# BartendingRobotPCB.net
KiCad netlist of a schematic drawn in EAGLE
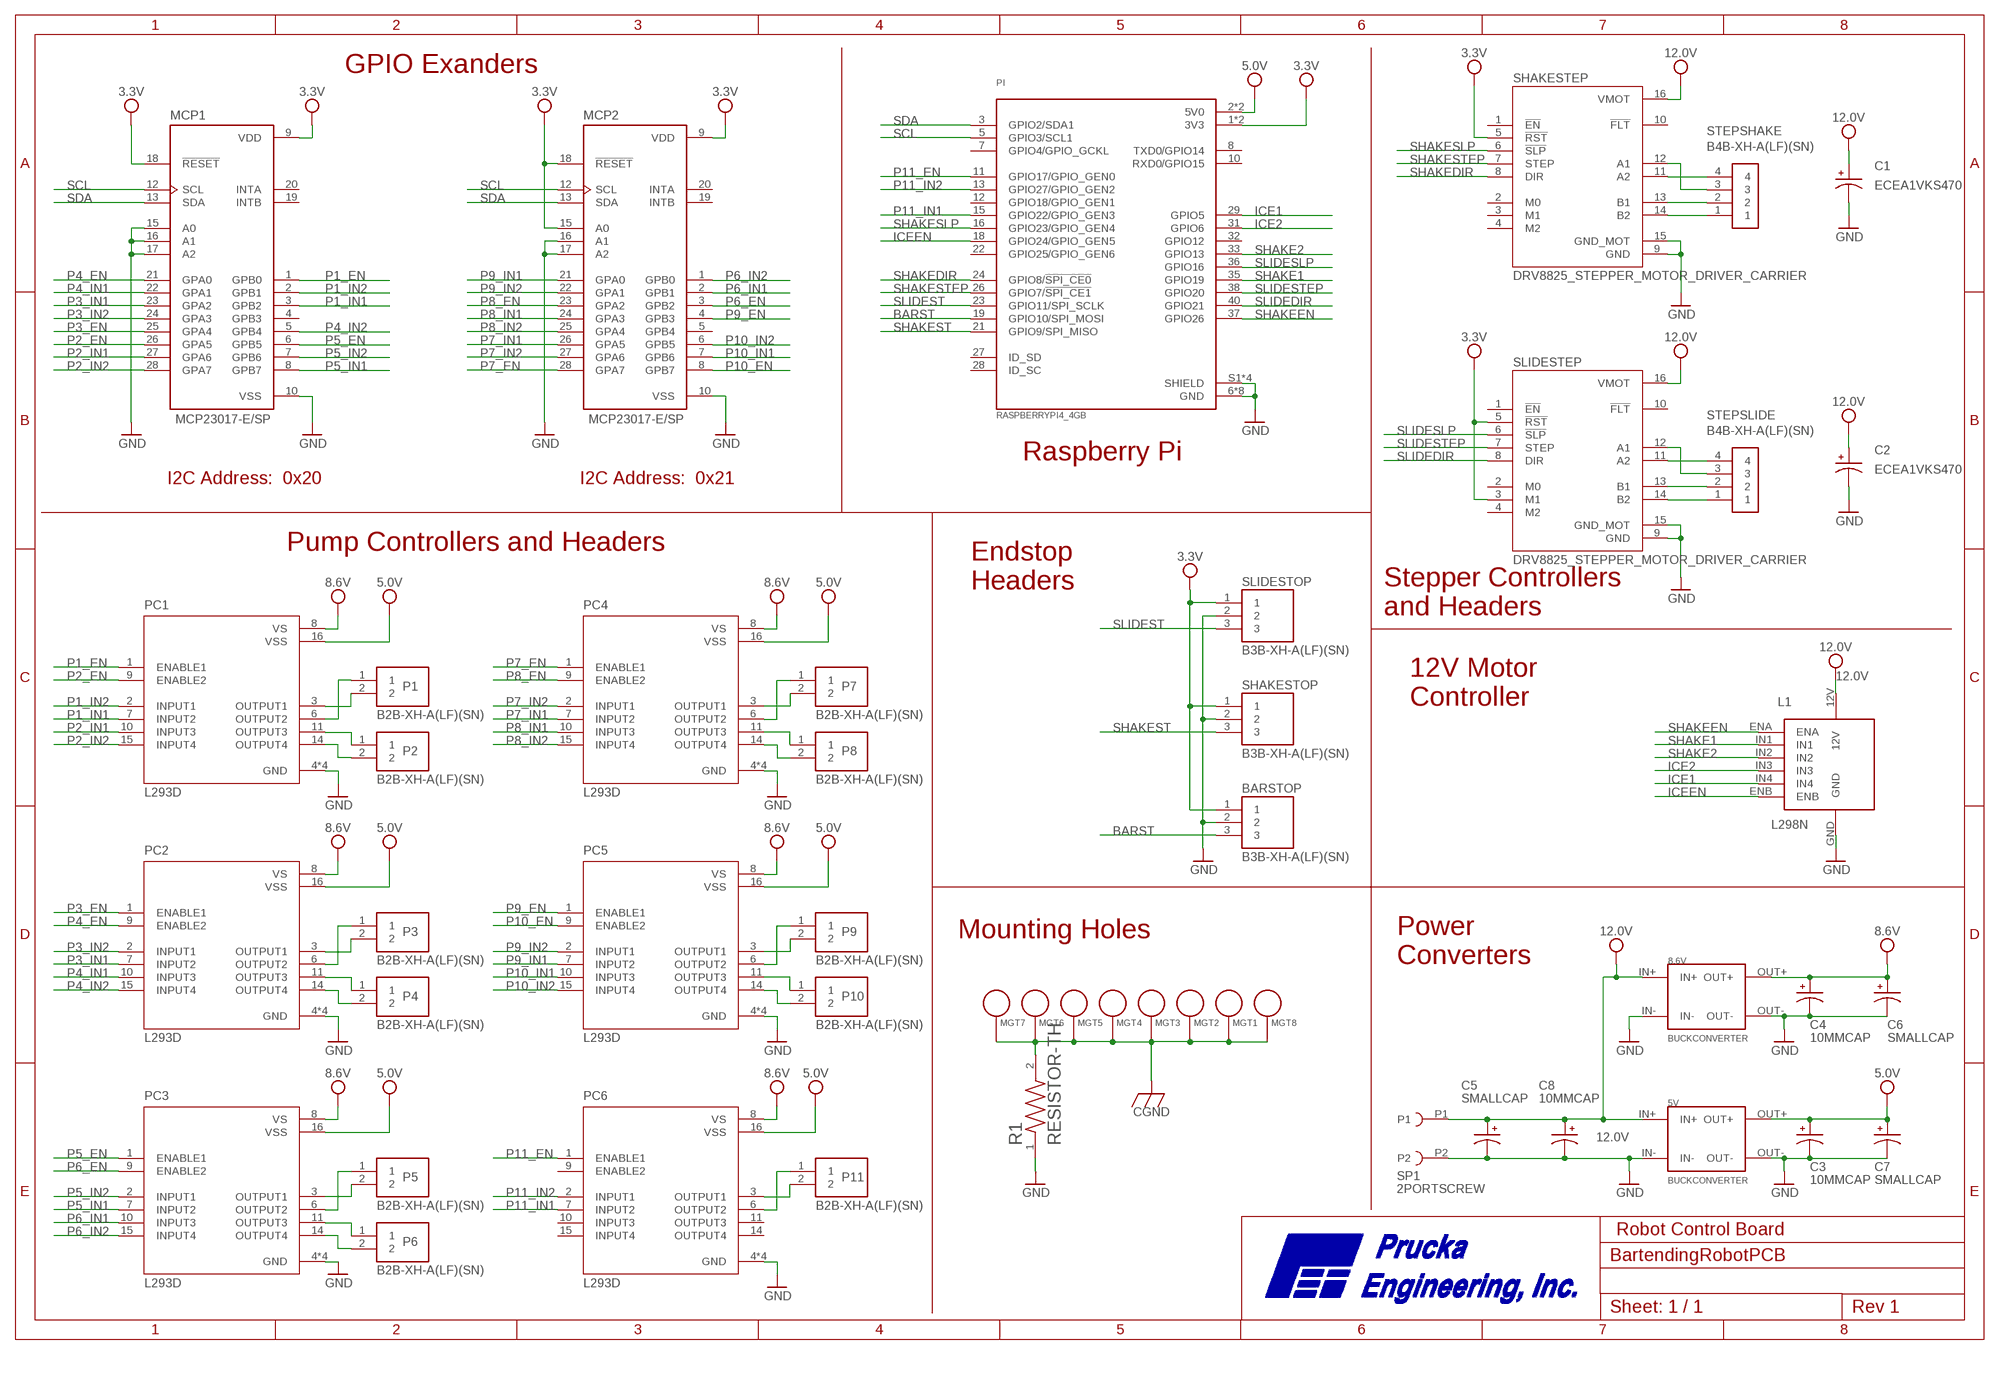
[diagram p0: schematic, sheet 1]

(export (version "E")
  (design (tool "Eeschema 10.0.6"))
  (components
    (comp (ref "5V")
      (value "BUCKCONVERTER")
      (footprint "eagle-import:BUCKCONVERTER")
      (libsource (lib "eagle-import") (part "BUCKCONVERTER"))
    )
    (comp (ref "8.6V")
      (value "BUCKCONVERTER")
      (footprint "eagle-import:BUCKCONVERTER")
      (libsource (lib "eagle-import") (part "BUCKCONVERTER"))
    )
    (comp (ref "BARSTOP")
      (value "B3B-XH-A(LF)(SN)")
      (footprint "eagle-import:JST_B3B-XH-A(LF)(SN)")
      (fields (field (name "MF") "JST Sales"))
      (libsource (lib "eagle-import") (part "B3B-XH-A(LF)(SN)"))
    )
    (comp (ref "C1")
      (value "ECEA1VKS470")
      (footprint "eagle-import:CAPPRD250W45D800H500")
      (fields (field (name "MF") "PANASONIC"))
      (libsource (lib "eagle-import") (part "ECEA1VKS470"))
    )
    (comp (ref "C2")
      (value "ECEA1VKS470")
      (footprint "eagle-import:CAPPRD250W45D800H500")
      (fields (field (name "MF") "PANASONIC"))
      (libsource (lib "eagle-import") (part "ECEA1VKS470"))
    )
    (comp (ref "C3")
      (value "10MMCAP")
      (footprint "eagle-import:10MMCAP")
      (libsource (lib "eagle-import") (part "10MMCAP"))
    )
    (comp (ref "C4")
      (value "10MMCAP")
      (footprint "eagle-import:10MMCAP")
      (libsource (lib "eagle-import") (part "10MMCAP"))
    )
    (comp (ref "C5")
      (value "SMALLCAP")
      (footprint "eagle-import:SMALLCAP")
      (libsource (lib "eagle-import") (part "SMALLCAP"))
    )
    (comp (ref "C6")
      (value "SMALLCAP")
      (footprint "eagle-import:SMALLCAP")
      (libsource (lib "eagle-import") (part "SMALLCAP"))
    )
    (comp (ref "C7")
      (value "SMALLCAP")
      (footprint "eagle-import:SMALLCAP")
      (libsource (lib "eagle-import") (part "SMALLCAP"))
    )
    (comp (ref "C8")
      (value "10MMCAP")
      (footprint "eagle-import:10MMCAP")
      (libsource (lib "eagle-import") (part "10MMCAP"))
    )
    (comp (ref "L1")
      (value "L298N")
      (footprint "eagle-import:L298N")
      (libsource (lib "eagle-import") (part "L298N"))
    )
    (comp (ref "MCP1")
      (value "MCP23017-E/SP")
      (footprint "eagle-import:DIP787W45P254L3556H508Q28")
      (fields (field (name "MF") "Microchip"))
      (libsource (lib "eagle-import") (part "MCP23017-E/SP"))
    )
    (comp (ref "MCP2")
      (value "MCP23017-E/SP")
      (footprint "eagle-import:DIP787W45P254L3556H508Q28")
      (fields (field (name "MF") "Microchip"))
      (libsource (lib "eagle-import") (part "MCP23017-E/SP"))
    )
    (comp (ref "MGT1")
      (value "MOUNTING_HOLE")
      (footprint "eagle-import:MOUNTING_HOLE")
      (libsource (lib "eagle-import") (part "MOUNTING_HOLE"))
    )
    (comp (ref "MGT2")
      (value "MOUNTING_HOLE")
      (footprint "eagle-import:MOUNTING_HOLE")
      (libsource (lib "eagle-import") (part "MOUNTING_HOLE"))
    )
    (comp (ref "MGT3")
      (value "MOUNTING_HOLE")
      (footprint "eagle-import:MOUNTING_HOLE")
      (libsource (lib "eagle-import") (part "MOUNTING_HOLE"))
    )
    (comp (ref "MGT4")
      (value "MOUNTING_HOLE")
      (footprint "eagle-import:MOUNTING_HOLE")
      (libsource (lib "eagle-import") (part "MOUNTING_HOLE"))
    )
    (comp (ref "MGT5")
      (value "MOUNTING_HOLE")
      (footprint "eagle-import:MOUNTING_HOLE")
      (libsource (lib "eagle-import") (part "MOUNTING_HOLE"))
    )
    (comp (ref "MGT6")
      (value "MOUNTING_HOLE")
      (footprint "eagle-import:MOUNTING_HOLE")
      (libsource (lib "eagle-import") (part "MOUNTING_HOLE"))
    )
    (comp (ref "MGT7")
      (value "MOUNTING_HOLE")
      (footprint "eagle-import:MOUNTING_HOLE")
      (libsource (lib "eagle-import") (part "MOUNTING_HOLE"))
    )
    (comp (ref "MGT8")
      (value "MOUNTING_HOLE")
      (footprint "eagle-import:MOUNTING_HOLE")
      (libsource (lib "eagle-import") (part "MOUNTING_HOLE"))
    )
    (comp (ref "P1")
      (value "B2B-XH-A(LF)(SN)")
      (footprint "eagle-import:JST_B2B-XH-A(LF)(SN)")
      (fields (field (name "MF") "JST Sales"))
      (libsource (lib "eagle-import") (part "B2B-XH-A(LF)(SN)"))
    )
    (comp (ref "P2")
      (value "B2B-XH-A(LF)(SN)")
      (footprint "eagle-import:JST_B2B-XH-A(LF)(SN)")
      (fields (field (name "MF") "JST Sales"))
      (libsource (lib "eagle-import") (part "B2B-XH-A(LF)(SN)"))
    )
    (comp (ref "P3")
      (value "B2B-XH-A(LF)(SN)")
      (footprint "eagle-import:JST_B2B-XH-A(LF)(SN)")
      (fields (field (name "MF") "JST Sales"))
      (libsource (lib "eagle-import") (part "B2B-XH-A(LF)(SN)"))
    )
    (comp (ref "P4")
      (value "B2B-XH-A(LF)(SN)")
      (footprint "eagle-import:JST_B2B-XH-A(LF)(SN)")
      (fields (field (name "MF") "JST Sales"))
      (libsource (lib "eagle-import") (part "B2B-XH-A(LF)(SN)"))
    )
    (comp (ref "P5")
      (value "B2B-XH-A(LF)(SN)")
      (footprint "eagle-import:JST_B2B-XH-A(LF)(SN)")
      (fields (field (name "MF") "JST Sales"))
      (libsource (lib "eagle-import") (part "B2B-XH-A(LF)(SN)"))
    )
    (comp (ref "P6")
      (value "B2B-XH-A(LF)(SN)")
      (footprint "eagle-import:JST_B2B-XH-A(LF)(SN)")
      (fields (field (name "MF") "JST Sales"))
      (libsource (lib "eagle-import") (part "B2B-XH-A(LF)(SN)"))
    )
    (comp (ref "P7")
      (value "B2B-XH-A(LF)(SN)")
      (footprint "eagle-import:JST_B2B-XH-A(LF)(SN)")
      (fields (field (name "MF") "JST Sales"))
      (libsource (lib "eagle-import") (part "B2B-XH-A(LF)(SN)"))
    )
    (comp (ref "P8")
      (value "B2B-XH-A(LF)(SN)")
      (footprint "eagle-import:JST_B2B-XH-A(LF)(SN)")
      (fields (field (name "MF") "JST Sales"))
      (libsource (lib "eagle-import") (part "B2B-XH-A(LF)(SN)"))
    )
    (comp (ref "P9")
      (value "B2B-XH-A(LF)(SN)")
      (footprint "eagle-import:JST_B2B-XH-A(LF)(SN)")
      (fields (field (name "MF") "JST Sales"))
      (libsource (lib "eagle-import") (part "B2B-XH-A(LF)(SN)"))
    )
    (comp (ref "P10")
      (value "B2B-XH-A(LF)(SN)")
      (footprint "eagle-import:JST_B2B-XH-A(LF)(SN)")
      (fields (field (name "MF") "JST Sales"))
      (libsource (lib "eagle-import") (part "B2B-XH-A(LF)(SN)"))
    )
    (comp (ref "P11")
      (value "B2B-XH-A(LF)(SN)")
      (footprint "eagle-import:JST_B2B-XH-A(LF)(SN)")
      (fields (field (name "MF") "JST Sales"))
      (libsource (lib "eagle-import") (part "B2B-XH-A(LF)(SN)"))
    )
    (comp (ref "PC1")
      (value "L293D")
      (footprint "eagle-import:DIP880W50P254L2000H510Q16")
      (fields (field (name "MANUFACTURER") "ST Microelectronics"))
      (libsource (lib "eagle-import") (part "L293D"))
    )
    (comp (ref "PC2")
      (value "L293D")
      (footprint "eagle-import:DIP880W50P254L2000H510Q16")
      (fields (field (name "MANUFACTURER") "ST Microelectronics"))
      (libsource (lib "eagle-import") (part "L293D"))
    )
    (comp (ref "PC3")
      (value "L293D")
      (footprint "eagle-import:DIP880W50P254L2000H510Q16")
      (fields (field (name "MANUFACTURER") "ST Microelectronics"))
      (libsource (lib "eagle-import") (part "L293D"))
    )
    (comp (ref "PC4")
      (value "L293D")
      (footprint "eagle-import:DIP880W50P254L2000H510Q16")
      (fields (field (name "MANUFACTURER") "ST Microelectronics"))
      (libsource (lib "eagle-import") (part "L293D"))
    )
    (comp (ref "PC5")
      (value "L293D")
      (footprint "eagle-import:DIP880W50P254L2000H510Q16")
      (fields (field (name "MANUFACTURER") "ST Microelectronics"))
      (libsource (lib "eagle-import") (part "L293D"))
    )
    (comp (ref "PC6")
      (value "L293D")
      (footprint "eagle-import:DIP880W50P254L2000H510Q16")
      (fields (field (name "MANUFACTURER") "ST Microelectronics"))
      (libsource (lib "eagle-import") (part "L293D"))
    )
    (comp (ref "PI")
      (value "RASPBERRYPI4_4GB")
      (footprint "eagle-import:MODULE_RASPBERRYPI4_4GB")
      (fields (field (name "MANUFACTURER") "Raspberry Pi"))
      (libsource (lib "eagle-import") (part "RASPBERRYPI4_4GB"))
    )
    (comp (ref "R1")
      (value "RESISTOR-TH")
      (footprint "eagle-import:RESAD700W45L350D185")
      (fields (field (name "MANUFACTURER") "TE Connectivity"))
      (libsource (lib "eagle-import") (part "RESISTOR-TH"))
    )
    (comp (ref "SHAKESTEP")
      (value "DRV8825_STEPPER_MOTOR_DRIVER_CARRIER")
      (footprint "eagle-import:IC_DRV8825_STEPPER_MOTOR_DRIVER_CARRIER")
      (fields (field (name "MF") "Pololu") (field (name "MP") "DRV8825 STEPPER MOTOR DRIVER CARRIER"))
      (libsource (lib "eagle-import") (part "DRV8825_STEPPER_MOTOR_DRIVER_CARRIER"))
    )
    (comp (ref "SHAKESTOP")
      (value "B3B-XH-A(LF)(SN)")
      (footprint "eagle-import:JST_B3B-XH-A(LF)(SN)")
      (fields (field (name "MF") "JST Sales"))
      (libsource (lib "eagle-import") (part "B3B-XH-A(LF)(SN)"))
    )
    (comp (ref "SLIDESTEP")
      (value "DRV8825_STEPPER_MOTOR_DRIVER_CARRIER")
      (footprint "eagle-import:IC_DRV8825_STEPPER_MOTOR_DRIVER_CARRIER")
      (fields (field (name "MF") "Pololu") (field (name "MP") "DRV8825 STEPPER MOTOR DRIVER CARRIER"))
      (libsource (lib "eagle-import") (part "DRV8825_STEPPER_MOTOR_DRIVER_CARRIER"))
    )
    (comp (ref "SLIDESTOP")
      (value "B3B-XH-A(LF)(SN)")
      (footprint "eagle-import:JST_B3B-XH-A(LF)(SN)")
      (fields (field (name "MF") "JST Sales"))
      (libsource (lib "eagle-import") (part "B3B-XH-A(LF)(SN)"))
    )
    (comp (ref "SP1")
      (value "2PORTSCREW")
      (footprint "eagle-import:2PORTSCREW")
      (libsource (lib "eagle-import") (part "2PORTSCREW"))
    )
    (comp (ref "STEPSHAKE")
      (value "B4B-XH-A(LF)(SN)")
      (footprint "eagle-import:JST_B4B-XH-A(LF)(SN)")
      (fields (field (name "MANUFACTURER") " JST Sales America Inc"))
      (libsource (lib "eagle-import") (part "B4B-XH-A(LF)(SN)"))
    )
    (comp (ref "STEPSLIDE")
      (value "B4B-XH-A(LF)(SN)")
      (footprint "eagle-import:JST_B4B-XH-A(LF)(SN)")
      (fields (field (name "MANUFACTURER") " JST Sales America Inc"))
      (libsource (lib "eagle-import") (part "B4B-XH-A(LF)(SN)"))
    )
  )
  (nets
    (net (code "1") (name "/BARST") (class "Default")
      (node (ref "BARSTOP") (pin "3") (pinfunction "3_3") (pintype "passive"))
      (node (ref "PI") (pin "19") (pinfunction "GPIO10/SPI_MOSI_19") (pintype "bidirectional"))
    )
    (net (code "2") (name "/ICE1") (class "Default")
      (node (ref "L1") (pin "IN4") (pinfunction "IN4_IN4") (pintype "bidirectional"))
      (node (ref "PI") (pin "29") (pinfunction "GPIO5_29") (pintype "bidirectional"))
    )
    (net (code "3") (name "/ICE2") (class "Default")
      (node (ref "L1") (pin "IN3") (pinfunction "IN3_IN3") (pintype "bidirectional"))
      (node (ref "PI") (pin "31") (pinfunction "GPIO6_31") (pintype "bidirectional"))
    )
    (net (code "4") (name "/ICEEN") (class "Default")
      (node (ref "L1") (pin "ENB") (pinfunction "ENB_ENB") (pintype "bidirectional"))
      (node (ref "PI") (pin "18") (pinfunction "GPIO24/GPIO_GEN5_18") (pintype "bidirectional"))
    )
    (net (code "5") (name "/P1_EN") (class "Default")
      (node (ref "MCP1") (pin "1") (pinfunction "GPB0_1") (pintype "bidirectional"))
      (node (ref "PC1") (pin "1") (pinfunction "ENABLE1_1") (pintype "input"))
    )
    (net (code "6") (name "/P1_IN1") (class "Default")
      (node (ref "MCP1") (pin "3") (pinfunction "GPB2_3") (pintype "bidirectional"))
      (node (ref "PC1") (pin "7") (pinfunction "INPUT2_7") (pintype "input"))
    )
    (net (code "7") (name "/P1_IN2") (class "Default")
      (node (ref "MCP1") (pin "2") (pinfunction "GPB1_2") (pintype "bidirectional"))
      (node (ref "PC1") (pin "2") (pinfunction "INPUT1_2") (pintype "input"))
    )
    (net (code "8") (name "/P2_EN") (class "Default")
      (node (ref "MCP1") (pin "26") (pinfunction "GPA5_26") (pintype "bidirectional"))
      (node (ref "PC1") (pin "9") (pinfunction "ENABLE2_9") (pintype "input"))
    )
    (net (code "9") (name "/P2_IN1") (class "Default")
      (node (ref "MCP1") (pin "27") (pinfunction "GPA6_27") (pintype "bidirectional"))
      (node (ref "PC1") (pin "10") (pinfunction "INPUT3_10") (pintype "input"))
    )
    (net (code "10") (name "/P2_IN2") (class "Default")
      (node (ref "MCP1") (pin "28") (pinfunction "GPA7_28") (pintype "bidirectional"))
      (node (ref "PC1") (pin "15") (pinfunction "INPUT4_15") (pintype "input"))
    )
    (net (code "11") (name "/P3_EN") (class "Default")
      (node (ref "MCP1") (pin "25") (pinfunction "GPA4_25") (pintype "bidirectional"))
      (node (ref "PC2") (pin "1") (pinfunction "ENABLE1_1") (pintype "input"))
    )
    (net (code "12") (name "/P3_IN1") (class "Default")
      (node (ref "MCP1") (pin "23") (pinfunction "GPA2_23") (pintype "bidirectional"))
      (node (ref "PC2") (pin "7") (pinfunction "INPUT2_7") (pintype "input"))
    )
    (net (code "13") (name "/P3_IN2") (class "Default")
      (node (ref "MCP1") (pin "24") (pinfunction "GPA3_24") (pintype "bidirectional"))
      (node (ref "PC2") (pin "2") (pinfunction "INPUT1_2") (pintype "input"))
    )
    (net (code "14") (name "/P4_EN") (class "Default")
      (node (ref "MCP1") (pin "21") (pinfunction "GPA0_21") (pintype "bidirectional"))
      (node (ref "PC2") (pin "9") (pinfunction "ENABLE2_9") (pintype "input"))
    )
    (net (code "15") (name "/P4_IN1") (class "Default")
      (node (ref "MCP1") (pin "22") (pinfunction "GPA1_22") (pintype "bidirectional"))
      (node (ref "PC2") (pin "10") (pinfunction "INPUT3_10") (pintype "input"))
    )
    (net (code "16") (name "/P4_IN2") (class "Default")
      (node (ref "MCP1") (pin "5") (pinfunction "GPB4_5") (pintype "bidirectional"))
      (node (ref "PC2") (pin "15") (pinfunction "INPUT4_15") (pintype "input"))
    )
    (net (code "17") (name "/P5_EN") (class "Default")
      (node (ref "MCP1") (pin "6") (pinfunction "GPB5_6") (pintype "bidirectional"))
      (node (ref "PC3") (pin "1") (pinfunction "ENABLE1_1") (pintype "input"))
    )
    (net (code "18") (name "/P5_IN1") (class "Default")
      (node (ref "MCP1") (pin "8") (pinfunction "GPB7_8") (pintype "bidirectional"))
      (node (ref "PC3") (pin "7") (pinfunction "INPUT2_7") (pintype "input"))
    )
    (net (code "19") (name "/P5_IN2") (class "Default")
      (node (ref "MCP1") (pin "7") (pinfunction "GPB6_7") (pintype "bidirectional"))
      (node (ref "PC3") (pin "2") (pinfunction "INPUT1_2") (pintype "input"))
    )
    (net (code "20") (name "/P6_EN") (class "Default")
      (node (ref "MCP2") (pin "3") (pinfunction "GPB2_3") (pintype "bidirectional"))
      (node (ref "PC3") (pin "9") (pinfunction "ENABLE2_9") (pintype "input"))
    )
    (net (code "21") (name "/P6_IN1") (class "Default")
      (node (ref "MCP2") (pin "2") (pinfunction "GPB1_2") (pintype "bidirectional"))
      (node (ref "PC3") (pin "10") (pinfunction "INPUT3_10") (pintype "input"))
    )
    (net (code "22") (name "/P6_IN2") (class "Default")
      (node (ref "MCP2") (pin "1") (pinfunction "GPB0_1") (pintype "bidirectional"))
      (node (ref "PC3") (pin "15") (pinfunction "INPUT4_15") (pintype "input"))
    )
    (net (code "23") (name "/P7_EN") (class "Default")
      (node (ref "MCP2") (pin "28") (pinfunction "GPA7_28") (pintype "bidirectional"))
      (node (ref "PC4") (pin "1") (pinfunction "ENABLE1_1") (pintype "input"))
    )
    (net (code "24") (name "/P7_IN1") (class "Default")
      (node (ref "MCP2") (pin "26") (pinfunction "GPA5_26") (pintype "bidirectional"))
      (node (ref "PC4") (pin "7") (pinfunction "INPUT2_7") (pintype "input"))
    )
    (net (code "25") (name "/P7_IN2") (class "Default")
      (node (ref "MCP2") (pin "27") (pinfunction "GPA6_27") (pintype "bidirectional"))
      (node (ref "PC4") (pin "2") (pinfunction "INPUT1_2") (pintype "input"))
    )
    (net (code "26") (name "/P8_EN") (class "Default")
      (node (ref "MCP2") (pin "23") (pinfunction "GPA2_23") (pintype "bidirectional"))
      (node (ref "PC4") (pin "9") (pinfunction "ENABLE2_9") (pintype "input"))
    )
    (net (code "27") (name "/P8_IN1") (class "Default")
      (node (ref "MCP2") (pin "24") (pinfunction "GPA3_24") (pintype "bidirectional"))
      (node (ref "PC4") (pin "10") (pinfunction "INPUT3_10") (pintype "input"))
    )
    (net (code "28") (name "/P8_IN2") (class "Default")
      (node (ref "MCP2") (pin "25") (pinfunction "GPA4_25") (pintype "bidirectional"))
      (node (ref "PC4") (pin "15") (pinfunction "INPUT4_15") (pintype "input"))
    )
    (net (code "29") (name "/P9_EN") (class "Default")
      (node (ref "MCP2") (pin "4") (pinfunction "GPB3_4") (pintype "bidirectional"))
      (node (ref "PC5") (pin "1") (pinfunction "ENABLE1_1") (pintype "input"))
    )
    (net (code "30") (name "/P9_IN1") (class "Default")
      (node (ref "MCP2") (pin "21") (pinfunction "GPA0_21") (pintype "bidirectional"))
      (node (ref "PC5") (pin "7") (pinfunction "INPUT2_7") (pintype "input"))
    )
    (net (code "31") (name "/P9_IN2") (class "Default")
      (node (ref "MCP2") (pin "22") (pinfunction "GPA1_22") (pintype "bidirectional"))
      (node (ref "PC5") (pin "2") (pinfunction "INPUT1_2") (pintype "input"))
    )
    (net (code "32") (name "/P10_EN") (class "Default")
      (node (ref "MCP2") (pin "8") (pinfunction "GPB7_8") (pintype "bidirectional"))
      (node (ref "PC5") (pin "9") (pinfunction "ENABLE2_9") (pintype "input"))
    )
    (net (code "33") (name "/P10_IN1") (class "Default")
      (node (ref "MCP2") (pin "7") (pinfunction "GPB6_7") (pintype "bidirectional"))
      (node (ref "PC5") (pin "10") (pinfunction "INPUT3_10") (pintype "input"))
    )
    (net (code "34") (name "/P10_IN2") (class "Default")
      (node (ref "MCP2") (pin "6") (pinfunction "GPB5_6") (pintype "bidirectional"))
      (node (ref "PC5") (pin "15") (pinfunction "INPUT4_15") (pintype "input"))
    )
    (net (code "35") (name "/P11_EN") (class "Default")
      (node (ref "PC6") (pin "1") (pinfunction "ENABLE1_1") (pintype "input"))
      (node (ref "PI") (pin "11") (pinfunction "GPIO17/GPIO_GEN0_11") (pintype "bidirectional"))
    )
    (net (code "36") (name "/P11_IN1") (class "Default")
      (node (ref "PC6") (pin "7") (pinfunction "INPUT2_7") (pintype "input"))
      (node (ref "PI") (pin "15") (pinfunction "GPIO22/GPIO_GEN3_15") (pintype "bidirectional"))
    )
    (net (code "37") (name "/P11_IN2") (class "Default")
      (node (ref "PC6") (pin "2") (pinfunction "INPUT1_2") (pintype "input"))
      (node (ref "PI") (pin "13") (pinfunction "GPIO27/GPIO_GEN2_13") (pintype "bidirectional"))
    )
    (net (code "38") (name "/SCL") (class "Default")
      (node (ref "MCP1") (pin "12") (pinfunction "SCL_12") (pintype "input"))
      (node (ref "MCP2") (pin "12") (pinfunction "SCL_12") (pintype "input"))
      (node (ref "PI") (pin "5") (pinfunction "GPIO3/SCL1_5") (pintype "bidirectional"))
    )
    (net (code "39") (name "/SDA") (class "Default")
      (node (ref "MCP1") (pin "13") (pinfunction "SDA_13") (pintype "bidirectional"))
      (node (ref "MCP2") (pin "13") (pinfunction "SDA_13") (pintype "bidirectional"))
      (node (ref "PI") (pin "3") (pinfunction "GPIO2/SDA1_3") (pintype "bidirectional"))
    )
    (net (code "40") (name "/SHAKE1") (class "Default")
      (node (ref "L1") (pin "IN1") (pinfunction "IN1_IN1") (pintype "bidirectional"))
      (node (ref "PI") (pin "35") (pinfunction "GPIO19_35") (pintype "bidirectional"))
    )
    (net (code "41") (name "/SHAKE2") (class "Default")
      (node (ref "L1") (pin "IN2") (pinfunction "IN2_IN2") (pintype "bidirectional"))
      (node (ref "PI") (pin "33") (pinfunction "GPIO13_33") (pintype "bidirectional"))
    )
    (net (code "42") (name "/SHAKEDIR") (class "Default")
      (node (ref "PI") (pin "24") (pinfunction "GPIO8/~{SPI_CE0}_24") (pintype "bidirectional"))
      (node (ref "SHAKESTEP") (pin "8") (pinfunction "DIR_8") (pintype "input"))
    )
    (net (code "43") (name "/SHAKEEN") (class "Default")
      (node (ref "L1") (pin "ENA") (pinfunction "ENA_ENA") (pintype "bidirectional"))
      (node (ref "PI") (pin "37") (pinfunction "GPIO26_37") (pintype "bidirectional"))
    )
    (net (code "44") (name "/SHAKESLP") (class "Default")
      (node (ref "PI") (pin "16") (pinfunction "GPIO23/GPIO_GEN4_16") (pintype "bidirectional"))
      (node (ref "SHAKESTEP") (pin "6") (pinfunction "~{SLP}_6") (pintype "input"))
    )
    (net (code "45") (name "/SHAKEST") (class "Default")
      (node (ref "PI") (pin "21") (pinfunction "GPIO9/SPI_MISO_21") (pintype "bidirectional"))
      (node (ref "SHAKESTOP") (pin "3") (pinfunction "3_3") (pintype "passive"))
    )
    (net (code "46") (name "/SHAKESTEP") (class "Default")
      (node (ref "PI") (pin "26") (pinfunction "GPIO7/~{SPI_CE1}_26") (pintype "bidirectional"))
      (node (ref "SHAKESTEP") (pin "7") (pinfunction "STEP_7") (pintype "input"))
    )
    (net (code "47") (name "/SLIDEDIR") (class "Default")
      (node (ref "PI") (pin "40") (pinfunction "GPIO21_40") (pintype "bidirectional"))
      (node (ref "SLIDESTEP") (pin "8") (pinfunction "DIR_8") (pintype "input"))
    )
    (net (code "48") (name "/SLIDESLP") (class "Default")
      (node (ref "PI") (pin "36") (pinfunction "GPIO16_36") (pintype "bidirectional"))
      (node (ref "SLIDESTEP") (pin "6") (pinfunction "~{SLP}_6") (pintype "input"))
    )
    (net (code "49") (name "/SLIDEST") (class "Default")
      (node (ref "PI") (pin "23") (pinfunction "GPIO11/SPI_SCLK_23") (pintype "bidirectional"))
      (node (ref "SLIDESTOP") (pin "3") (pinfunction "3_3") (pintype "passive"))
    )
    (net (code "50") (name "/SLIDESTEP") (class "Default")
      (node (ref "PI") (pin "38") (pinfunction "GPIO20_38") (pintype "bidirectional"))
      (node (ref "SLIDESTEP") (pin "7") (pinfunction "STEP_7") (pintype "input"))
    )
    (net (code "51") (name "3.3V") (class "Default")
      (node (ref "BARSTOP") (pin "1") (pinfunction "1_1") (pintype "passive"))
      (node (ref "MCP1") (pin "18") (pinfunction "~{RESET}_18") (pintype "input"))
      (node (ref "MCP1") (pin "9") (pinfunction "VDD_9") (pintype "power_in"))
      (node (ref "MCP2") (pin "15") (pinfunction "A0_15") (pintype "input"))
      (node (ref "MCP2") (pin "18") (pinfunction "~{RESET}_18") (pintype "input"))
      (node (ref "MCP2") (pin "9") (pinfunction "VDD_9") (pintype "power_in"))
      (node (ref "PI") (pin "1") (pinfunction "3V3_1") (pintype "power_in"))
      (node (ref "PI") (pin "17") (pinfunction "3V3_17") (pintype "power_in"))
      (node (ref "SHAKESTEP") (pin "5") (pinfunction "~{RST}_5") (pintype "input"))
      (node (ref "SHAKESTOP") (pin "1") (pinfunction "1_1") (pintype "passive"))
      (node (ref "SLIDESTEP") (pin "3") (pinfunction "M1_3") (pintype "input"))
      (node (ref "SLIDESTEP") (pin "5") (pinfunction "~{RST}_5") (pintype "input"))
      (node (ref "SLIDESTOP") (pin "1") (pinfunction "1_1") (pintype "passive"))
    )
    (net (code "52") (name "5.0V") (class "Default")
      (node (ref "5V") (pin "OUT+") (pinfunction "OUT+_OUT+") (pintype "bidirectional"))
      (node (ref "C3") (pin "+") (pinfunction "P_+") (pintype "passive"))
      (node (ref "C7") (pin "+") (pinfunction "P_+") (pintype "passive"))
      (node (ref "PC1") (pin "16") (pinfunction "VSS_16") (pintype "power_in"))
      (node (ref "PC2") (pin "16") (pinfunction "VSS_16") (pintype "power_in"))
      (node (ref "PC3") (pin "16") (pinfunction "VSS_16") (pintype "power_in"))
      (node (ref "PC4") (pin "16") (pinfunction "VSS_16") (pintype "power_in"))
      (node (ref "PC5") (pin "16") (pinfunction "VSS_16") (pintype "power_in"))
      (node (ref "PC6") (pin "16") (pinfunction "VSS_16") (pintype "power_in"))
      (node (ref "PI") (pin "2") (pinfunction "5V0_2") (pintype "power_in"))
      (node (ref "PI") (pin "4") (pinfunction "5V0_4") (pintype "power_in"))
    )
    (net (code "53") (name "8.6V") (class "Default")
      (node (ref "8.6V") (pin "OUT+") (pinfunction "OUT+_OUT+") (pintype "bidirectional"))
      (node (ref "C4") (pin "+") (pinfunction "P_+") (pintype "passive"))
      (node (ref "C6") (pin "+") (pinfunction "P_+") (pintype "passive"))
      (node (ref "PC1") (pin "8") (pinfunction "VS_8") (pintype "power_in"))
      (node (ref "PC2") (pin "8") (pinfunction "VS_8") (pintype "power_in"))
      (node (ref "PC3") (pin "8") (pinfunction "VS_8") (pintype "power_in"))
      (node (ref "PC4") (pin "8") (pinfunction "VS_8") (pintype "power_in"))
      (node (ref "PC5") (pin "8") (pinfunction "VS_8") (pintype "power_in"))
      (node (ref "PC6") (pin "8") (pinfunction "VS_8") (pintype "power_in"))
    )
    (net (code "54") (name "12.0V") (class "Default")
      (node (ref "5V") (pin "IN+") (pinfunction "IN+_IN+") (pintype "bidirectional"))
      (node (ref "8.6V") (pin "IN+") (pinfunction "IN+_IN+") (pintype "bidirectional"))
      (node (ref "C1") (pin "P") (pinfunction "P_P") (pintype "passive"))
      (node (ref "C2") (pin "P") (pinfunction "P_P") (pintype "passive"))
      (node (ref "C5") (pin "+") (pinfunction "P_+") (pintype "passive"))
      (node (ref "C8") (pin "+") (pinfunction "P_+") (pintype "passive"))
      (node (ref "L1") (pin "12V") (pinfunction "12V_12V") (pintype "bidirectional"))
      (node (ref "SHAKESTEP") (pin "16") (pinfunction "VMOT_16") (pintype "power_in"))
      (node (ref "SLIDESTEP") (pin "16") (pinfunction "VMOT_16") (pintype "power_in"))
      (node (ref "SP1") (pin "P1") (pinfunction "P1_P1") (pintype "bidirectional"))
    )
    (net (code "55") (name "CGND") (class "Default")
      (node (ref "MGT1") (pin "P$1") (pinfunction "P$1_P$1") (pintype "bidirectional"))
      (node (ref "MGT2") (pin "P$1") (pinfunction "P$1_P$1") (pintype "bidirectional"))
      (node (ref "MGT3") (pin "P$1") (pinfunction "P$1_P$1") (pintype "bidirectional"))
      (node (ref "MGT4") (pin "P$1") (pinfunction "P$1_P$1") (pintype "bidirectional"))
      (node (ref "MGT5") (pin "P$1") (pinfunction "P$1_P$1") (pintype "bidirectional"))
      (node (ref "MGT6") (pin "P$1") (pinfunction "P$1_P$1") (pintype "bidirectional"))
      (node (ref "MGT7") (pin "P$1") (pinfunction "P$1_P$1") (pintype "bidirectional"))
      (node (ref "MGT8") (pin "P$1") (pinfunction "P$1_P$1") (pintype "bidirectional"))
      (node (ref "R1") (pin "2") (pinfunction "2_2") (pintype "passive"))
    )
    (net (code "56") (name "GND") (class "Default")
      (node (ref "5V") (pin "IN-") (pinfunction "IN-_IN-") (pintype "bidirectional"))
      (node (ref "5V") (pin "OUT-") (pinfunction "OUT-_OUT-") (pintype "bidirectional"))
      (node (ref "8.6V") (pin "IN-") (pinfunction "IN-_IN-") (pintype "bidirectional"))
      (node (ref "8.6V") (pin "OUT-") (pinfunction "OUT-_OUT-") (pintype "bidirectional"))
      (node (ref "BARSTOP") (pin "2") (pinfunction "2_2") (pintype "passive"))
      (node (ref "C1") (pin "N") (pinfunction "N_N") (pintype "passive"))
      (node (ref "C2") (pin "N") (pinfunction "N_N") (pintype "passive"))
      (node (ref "C3") (pin "-") (pinfunction "N_-") (pintype "passive"))
      (node (ref "C4") (pin "-") (pinfunction "N_-") (pintype "passive"))
      (node (ref "C5") (pin "-") (pinfunction "N_-") (pintype "passive"))
      (node (ref "C6") (pin "-") (pinfunction "N_-") (pintype "passive"))
      (node (ref "C7") (pin "-") (pinfunction "N_-") (pintype "passive"))
      (node (ref "C8") (pin "-") (pinfunction "N_-") (pintype "passive"))
      (node (ref "L1") (pin "GND") (pinfunction "GND_GND") (pintype "bidirectional"))
      (node (ref "MCP1") (pin "10") (pinfunction "VSS_10") (pintype "power_in"))
      (node (ref "MCP1") (pin "15") (pinfunction "A0_15") (pintype "input"))
      (node (ref "MCP1") (pin "16") (pinfunction "A1_16") (pintype "input"))
      (node (ref "MCP1") (pin "17") (pinfunction "A2_17") (pintype "input"))
      (node (ref "MCP2") (pin "10") (pinfunction "VSS_10") (pintype "power_in"))
      (node (ref "MCP2") (pin "16") (pinfunction "A1_16") (pintype "input"))
      (node (ref "MCP2") (pin "17") (pinfunction "A2_17") (pintype "input"))
      (node (ref "PC1") (pin "12") (pinfunction "GND_12") (pintype "power_in"))
      (node (ref "PC1") (pin "13") (pinfunction "GND_13") (pintype "power_in"))
      (node (ref "PC1") (pin "4") (pinfunction "GND_4") (pintype "power_in"))
      (node (ref "PC1") (pin "5") (pinfunction "GND_5") (pintype "power_in"))
      (node (ref "PC2") (pin "12") (pinfunction "GND_12") (pintype "power_in"))
      (node (ref "PC2") (pin "13") (pinfunction "GND_13") (pintype "power_in"))
      (node (ref "PC2") (pin "4") (pinfunction "GND_4") (pintype "power_in"))
      (node (ref "PC2") (pin "5") (pinfunction "GND_5") (pintype "power_in"))
      (node (ref "PC3") (pin "12") (pinfunction "GND_12") (pintype "power_in"))
      (node (ref "PC3") (pin "13") (pinfunction "GND_13") (pintype "power_in"))
      (node (ref "PC3") (pin "4") (pinfunction "GND_4") (pintype "power_in"))
      (node (ref "PC3") (pin "5") (pinfunction "GND_5") (pintype "power_in"))
      (node (ref "PC4") (pin "12") (pinfunction "GND_12") (pintype "power_in"))
      (node (ref "PC4") (pin "13") (pinfunction "GND_13") (pintype "power_in"))
      (node (ref "PC4") (pin "4") (pinfunction "GND_4") (pintype "power_in"))
      (node (ref "PC4") (pin "5") (pinfunction "GND_5") (pintype "power_in"))
      (node (ref "PC5") (pin "12") (pinfunction "GND_12") (pintype "power_in"))
      (node (ref "PC5") (pin "13") (pinfunction "GND_13") (pintype "power_in"))
      (node (ref "PC5") (pin "4") (pinfunction "GND_4") (pintype "power_in"))
      (node (ref "PC5") (pin "5") (pinfunction "GND_5") (pintype "power_in"))
      (node (ref "PC6") (pin "12") (pinfunction "GND_12") (pintype "power_in"))
      (node (ref "PC6") (pin "13") (pinfunction "GND_13") (pintype "power_in"))
      (node (ref "PC6") (pin "4") (pinfunction "GND_4") (pintype "power_in"))
      (node (ref "PC6") (pin "5") (pinfunction "GND_5") (pintype "power_in"))
      (node (ref "PI") (pin "14") (pinfunction "GND_14") (pintype "power_in"))
      (node (ref "PI") (pin "20") (pinfunction "GND_20") (pintype "power_in"))
      (node (ref "PI") (pin "25") (pinfunction "GND_25") (pintype "power_in"))
      (node (ref "PI") (pin "30") (pinfunction "GND_30") (pintype "power_in"))
      (node (ref "PI") (pin "34") (pinfunction "GND_34") (pintype "power_in"))
      (node (ref "PI") (pin "39") (pinfunction "GND_39") (pintype "power_in"))
      (node (ref "PI") (pin "6") (pinfunction "GND_6") (pintype "power_in"))
      (node (ref "PI") (pin "9") (pinfunction "GND_9") (pintype "power_in"))
      (node (ref "PI") (pin "S1") (pinfunction "SHIELD_S1") (pintype "power_in"))
      (node (ref "PI") (pin "S2") (pinfunction "SHIELD_S2") (pintype "power_in"))
      (node (ref "PI") (pin "S3") (pinfunction "SHIELD_S3") (pintype "power_in"))
      (node (ref "PI") (pin "S4") (pinfunction "SHIELD_S4") (pintype "power_in"))
      (node (ref "R1") (pin "1") (pinfunction "1_1") (pintype "passive"))
      (node (ref "SHAKESTEP") (pin "15") (pinfunction "GND_MOT_15") (pintype "power_in"))
      (node (ref "SHAKESTEP") (pin "9") (pinfunction "GND_9") (pintype "power_in"))
      (node (ref "SHAKESTOP") (pin "2") (pinfunction "2_2") (pintype "passive"))
      (node (ref "SLIDESTEP") (pin "15") (pinfunction "GND_MOT_15") (pintype "power_in"))
      (node (ref "SLIDESTEP") (pin "9") (pinfunction "GND_9") (pintype "power_in"))
      (node (ref "SLIDESTOP") (pin "2") (pinfunction "2_2") (pintype "passive"))
      (node (ref "SP1") (pin "P2") (pinfunction "P2_P2") (pintype "bidirectional"))
    )
    (net (code "57") (name "Net-(PC1-OUTPUT1)") (class "Default")
      (node (ref "P1") (pin "2") (pinfunction "2_2") (pintype "passive"))
      (node (ref "PC1") (pin "3") (pinfunction "OUTPUT1_3") (pintype "output"))
    )
    (net (code "58") (name "Net-(PC1-OUTPUT2)") (class "Default")
      (node (ref "P1") (pin "1") (pinfunction "1_1") (pintype "passive"))
      (node (ref "PC1") (pin "6") (pinfunction "OUTPUT2_6") (pintype "output"))
    )
    (net (code "59") (name "Net-(PC1-OUTPUT3)") (class "Default")
      (node (ref "P2") (pin "1") (pinfunction "1_1") (pintype "passive"))
      (node (ref "PC1") (pin "11") (pinfunction "OUTPUT3_11") (pintype "output"))
    )
    (net (code "60") (name "Net-(PC1-OUTPUT4)") (class "Default")
      (node (ref "P2") (pin "2") (pinfunction "2_2") (pintype "passive"))
      (node (ref "PC1") (pin "14") (pinfunction "OUTPUT4_14") (pintype "output"))
    )
    (net (code "61") (name "Net-(PC2-OUTPUT1)") (class "Default")
      (node (ref "P3") (pin "2") (pinfunction "2_2") (pintype "passive"))
      (node (ref "PC2") (pin "3") (pinfunction "OUTPUT1_3") (pintype "output"))
    )
    (net (code "62") (name "Net-(PC2-OUTPUT2)") (class "Default")
      (node (ref "P3") (pin "1") (pinfunction "1_1") (pintype "passive"))
      (node (ref "PC2") (pin "6") (pinfunction "OUTPUT2_6") (pintype "output"))
    )
    (net (code "63") (name "Net-(PC2-OUTPUT3)") (class "Default")
      (node (ref "P4") (pin "1") (pinfunction "1_1") (pintype "passive"))
      (node (ref "PC2") (pin "11") (pinfunction "OUTPUT3_11") (pintype "output"))
    )
    (net (code "64") (name "Net-(PC2-OUTPUT4)") (class "Default")
      (node (ref "P4") (pin "2") (pinfunction "2_2") (pintype "passive"))
      (node (ref "PC2") (pin "14") (pinfunction "OUTPUT4_14") (pintype "output"))
    )
    (net (code "65") (name "Net-(PC3-OUTPUT1)") (class "Default")
      (node (ref "P5") (pin "2") (pinfunction "2_2") (pintype "passive"))
      (node (ref "PC3") (pin "3") (pinfunction "OUTPUT1_3") (pintype "output"))
    )
    (net (code "66") (name "Net-(PC3-OUTPUT2)") (class "Default")
      (node (ref "P5") (pin "1") (pinfunction "1_1") (pintype "passive"))
      (node (ref "PC3") (pin "6") (pinfunction "OUTPUT2_6") (pintype "output"))
    )
    (net (code "67") (name "Net-(PC3-OUTPUT3)") (class "Default")
      (node (ref "P6") (pin "1") (pinfunction "1_1") (pintype "passive"))
      (node (ref "PC3") (pin "11") (pinfunction "OUTPUT3_11") (pintype "output"))
    )
    (net (code "68") (name "Net-(PC3-OUTPUT4)") (class "Default")
      (node (ref "P6") (pin "2") (pinfunction "2_2") (pintype "passive"))
      (node (ref "PC3") (pin "14") (pinfunction "OUTPUT4_14") (pintype "output"))
    )
    (net (code "69") (name "Net-(PC4-OUTPUT1)") (class "Default")
      (node (ref "P7") (pin "2") (pinfunction "2_2") (pintype "passive"))
      (node (ref "PC4") (pin "3") (pinfunction "OUTPUT1_3") (pintype "output"))
    )
    (net (code "70") (name "Net-(PC4-OUTPUT2)") (class "Default")
      (node (ref "P7") (pin "1") (pinfunction "1_1") (pintype "passive"))
      (node (ref "PC4") (pin "6") (pinfunction "OUTPUT2_6") (pintype "output"))
    )
    (net (code "71") (name "Net-(PC4-OUTPUT3)") (class "Default")
      (node (ref "P8") (pin "1") (pinfunction "1_1") (pintype "passive"))
      (node (ref "PC4") (pin "11") (pinfunction "OUTPUT3_11") (pintype "output"))
    )
    (net (code "72") (name "Net-(PC4-OUTPUT4)") (class "Default")
      (node (ref "P8") (pin "2") (pinfunction "2_2") (pintype "passive"))
      (node (ref "PC4") (pin "14") (pinfunction "OUTPUT4_14") (pintype "output"))
    )
    (net (code "73") (name "Net-(PC5-OUTPUT1)") (class "Default")
      (node (ref "P9") (pin "2") (pinfunction "2_2") (pintype "passive"))
      (node (ref "PC5") (pin "3") (pinfunction "OUTPUT1_3") (pintype "output"))
    )
    (net (code "74") (name "Net-(PC5-OUTPUT2)") (class "Default")
      (node (ref "P9") (pin "1") (pinfunction "1_1") (pintype "passive"))
      (node (ref "PC5") (pin "6") (pinfunction "OUTPUT2_6") (pintype "output"))
    )
    (net (code "75") (name "Net-(PC5-OUTPUT3)") (class "Default")
      (node (ref "P10") (pin "1") (pinfunction "1_1") (pintype "passive"))
      (node (ref "PC5") (pin "11") (pinfunction "OUTPUT3_11") (pintype "output"))
    )
    (net (code "76") (name "Net-(PC5-OUTPUT4)") (class "Default")
      (node (ref "P10") (pin "2") (pinfunction "2_2") (pintype "passive"))
      (node (ref "PC5") (pin "14") (pinfunction "OUTPUT4_14") (pintype "output"))
    )
    (net (code "77") (name "Net-(PC6-OUTPUT1)") (class "Default")
      (node (ref "P11") (pin "2") (pinfunction "2_2") (pintype "passive"))
      (node (ref "PC6") (pin "3") (pinfunction "OUTPUT1_3") (pintype "output"))
    )
    (net (code "78") (name "Net-(PC6-OUTPUT2)") (class "Default")
      (node (ref "P11") (pin "1") (pinfunction "1_1") (pintype "passive"))
      (node (ref "PC6") (pin "6") (pinfunction "OUTPUT2_6") (pintype "output"))
    )
    (net (code "79") (name "Net-(SHAKESTEP-A1)") (class "Default")
      (node (ref "SHAKESTEP") (pin "12") (pinfunction "A1_12") (pintype "output"))
      (node (ref "STEPSHAKE") (pin "3") (pinfunction "3_3") (pintype "passive"))
    )
    (net (code "80") (name "Net-(SHAKESTEP-A2)") (class "Default")
      (node (ref "SHAKESTEP") (pin "11") (pinfunction "A2_11") (pintype "output"))
      (node (ref "STEPSHAKE") (pin "4") (pinfunction "4_4") (pintype "passive"))
    )
    (net (code "81") (name "Net-(SHAKESTEP-B1)") (class "Default")
      (node (ref "SHAKESTEP") (pin "13") (pinfunction "B1_13") (pintype "output"))
      (node (ref "STEPSHAKE") (pin "2") (pinfunction "2_2") (pintype "passive"))
    )
    (net (code "82") (name "Net-(SHAKESTEP-B2)") (class "Default")
      (node (ref "SHAKESTEP") (pin "14") (pinfunction "B2_14") (pintype "output"))
      (node (ref "STEPSHAKE") (pin "1") (pinfunction "1_1") (pintype "passive"))
    )
    (net (code "83") (name "Net-(SLIDESTEP-A1)") (class "Default")
      (node (ref "SLIDESTEP") (pin "12") (pinfunction "A1_12") (pintype "output"))
      (node (ref "STEPSLIDE") (pin "3") (pinfunction "3_3") (pintype "passive"))
    )
    (net (code "84") (name "Net-(SLIDESTEP-A2)") (class "Default")
      (node (ref "SLIDESTEP") (pin "11") (pinfunction "A2_11") (pintype "output"))
      (node (ref "STEPSLIDE") (pin "4") (pinfunction "4_4") (pintype "passive"))
    )
    (net (code "85") (name "Net-(SLIDESTEP-B1)") (class "Default")
      (node (ref "SLIDESTEP") (pin "13") (pinfunction "B1_13") (pintype "output"))
      (node (ref "STEPSLIDE") (pin "2") (pinfunction "2_2") (pintype "passive"))
    )
    (net (code "86") (name "Net-(SLIDESTEP-B2)") (class "Default")
      (node (ref "SLIDESTEP") (pin "14") (pinfunction "B2_14") (pintype "output"))
      (node (ref "STEPSLIDE") (pin "1") (pinfunction "1_1") (pintype "passive"))
    )
    (net (code "87") (name "unconnected-(MCP1-GPB3-Pad4)") (class "Default")
      (node (ref "MCP1") (pin "4") (pinfunction "GPB3_4") (pintype "bidirectional"))
    )
    (net (code "88") (name "unconnected-(MCP1-INTA-Pad20)") (class "Default")
      (node (ref "MCP1") (pin "20") (pinfunction "INTA_20") (pintype "output"))
    )
    (net (code "89") (name "unconnected-(MCP1-INTB-Pad19)") (class "Default")
      (node (ref "MCP1") (pin "19") (pinfunction "INTB_19") (pintype "output"))
    )
    (net (code "90") (name "unconnected-(MCP2-GPB4-Pad5)") (class "Default")
      (node (ref "MCP2") (pin "5") (pinfunction "GPB4_5") (pintype "bidirectional"))
    )
    (net (code "91") (name "unconnected-(MCP2-INTA-Pad20)") (class "Default")
      (node (ref "MCP2") (pin "20") (pinfunction "INTA_20") (pintype "output"))
    )
    (net (code "92") (name "unconnected-(MCP2-INTB-Pad19)") (class "Default")
      (node (ref "MCP2") (pin "19") (pinfunction "INTB_19") (pintype "output"))
    )
    (net (code "93") (name "unconnected-(PC6-ENABLE2-Pad9)") (class "Default")
      (node (ref "PC6") (pin "9") (pinfunction "ENABLE2_9") (pintype "input"))
    )
    (net (code "94") (name "unconnected-(PC6-INPUT3-Pad10)") (class "Default")
      (node (ref "PC6") (pin "10") (pinfunction "INPUT3_10") (pintype "input"))
    )
    (net (code "95") (name "unconnected-(PC6-INPUT4-Pad15)") (class "Default")
      (node (ref "PC6") (pin "15") (pinfunction "INPUT4_15") (pintype "input"))
    )
    (net (code "96") (name "unconnected-(PC6-OUTPUT3-Pad11)") (class "Default")
      (node (ref "PC6") (pin "11") (pinfunction "OUTPUT3_11") (pintype "output"))
    )
    (net (code "97") (name "unconnected-(PC6-OUTPUT4-Pad14)") (class "Default")
      (node (ref "PC6") (pin "14") (pinfunction "OUTPUT4_14") (pintype "output"))
    )
    (net (code "98") (name "unconnected-(PI-GPIO4{slash}GPIO_GCKL-Pad7)") (class "Default")
      (node (ref "PI") (pin "7") (pinfunction "GPIO4/GPIO_GCKL_7") (pintype "bidirectional"))
    )
    (net (code "99") (name "unconnected-(PI-GPIO12-Pad32)") (class "Default")
      (node (ref "PI") (pin "32") (pinfunction "GPIO12_32") (pintype "bidirectional"))
    )
    (net (code "100") (name "unconnected-(PI-GPIO18{slash}GPIO_GEN1-Pad12)") (class "Default")
      (node (ref "PI") (pin "12") (pinfunction "GPIO18/GPIO_GEN1_12") (pintype "bidirectional"))
    )
    (net (code "101") (name "unconnected-(PI-GPIO25{slash}GPIO_GEN6-Pad22)") (class "Default")
      (node (ref "PI") (pin "22") (pinfunction "GPIO25/GPIO_GEN6_22") (pintype "bidirectional"))
    )
    (net (code "102") (name "unconnected-(PI-ID_SC-Pad28)") (class "Default")
      (node (ref "PI") (pin "28") (pinfunction "ID_SC_28") (pintype "bidirectional"))
    )
    (net (code "103") (name "unconnected-(PI-ID_SD-Pad27)") (class "Default")
      (node (ref "PI") (pin "27") (pinfunction "ID_SD_27") (pintype "bidirectional"))
    )
    (net (code "104") (name "unconnected-(PI-RXD0{slash}GPIO15-Pad10)") (class "Default")
      (node (ref "PI") (pin "10") (pinfunction "RXD0/GPIO15_10") (pintype "bidirectional"))
    )
    (net (code "105") (name "unconnected-(PI-TXD0{slash}GPIO14-Pad8)") (class "Default")
      (node (ref "PI") (pin "8") (pinfunction "TXD0/GPIO14_8") (pintype "bidirectional"))
    )
    (net (code "106") (name "unconnected-(SHAKESTEP-M0-Pad2)") (class "Default")
      (node (ref "SHAKESTEP") (pin "2") (pinfunction "M0_2") (pintype "input"))
    )
    (net (code "107") (name "unconnected-(SHAKESTEP-M1-Pad3)") (class "Default")
      (node (ref "SHAKESTEP") (pin "3") (pinfunction "M1_3") (pintype "input"))
    )
    (net (code "108") (name "unconnected-(SHAKESTEP-M2-Pad4)") (class "Default")
      (node (ref "SHAKESTEP") (pin "4") (pinfunction "M2_4") (pintype "input"))
    )
    (net (code "109") (name "unconnected-(SHAKESTEP-~{EN}-Pad1)") (class "Default")
      (node (ref "SHAKESTEP") (pin "1") (pinfunction "~{EN}_1") (pintype "input"))
    )
    (net (code "110") (name "unconnected-(SHAKESTEP-~{FLT}-Pad10)") (class "Default")
      (node (ref "SHAKESTEP") (pin "10") (pinfunction "~{FLT}_10") (pintype "output"))
    )
    (net (code "111") (name "unconnected-(SLIDESTEP-M0-Pad2)") (class "Default")
      (node (ref "SLIDESTEP") (pin "2") (pinfunction "M0_2") (pintype "input"))
    )
    (net (code "112") (name "unconnected-(SLIDESTEP-M2-Pad4)") (class "Default")
      (node (ref "SLIDESTEP") (pin "4") (pinfunction "M2_4") (pintype "input"))
    )
    (net (code "113") (name "unconnected-(SLIDESTEP-~{EN}-Pad1)") (class "Default")
      (node (ref "SLIDESTEP") (pin "1") (pinfunction "~{EN}_1") (pintype "input"))
    )
    (net (code "114") (name "unconnected-(SLIDESTEP-~{FLT}-Pad10)") (class "Default")
      (node (ref "SLIDESTEP") (pin "10") (pinfunction "~{FLT}_10") (pintype "output"))
    )
  )
)
